# Quectel-2560-v2_1.net
KiCad netlist of a schematic drawn in EAGLE
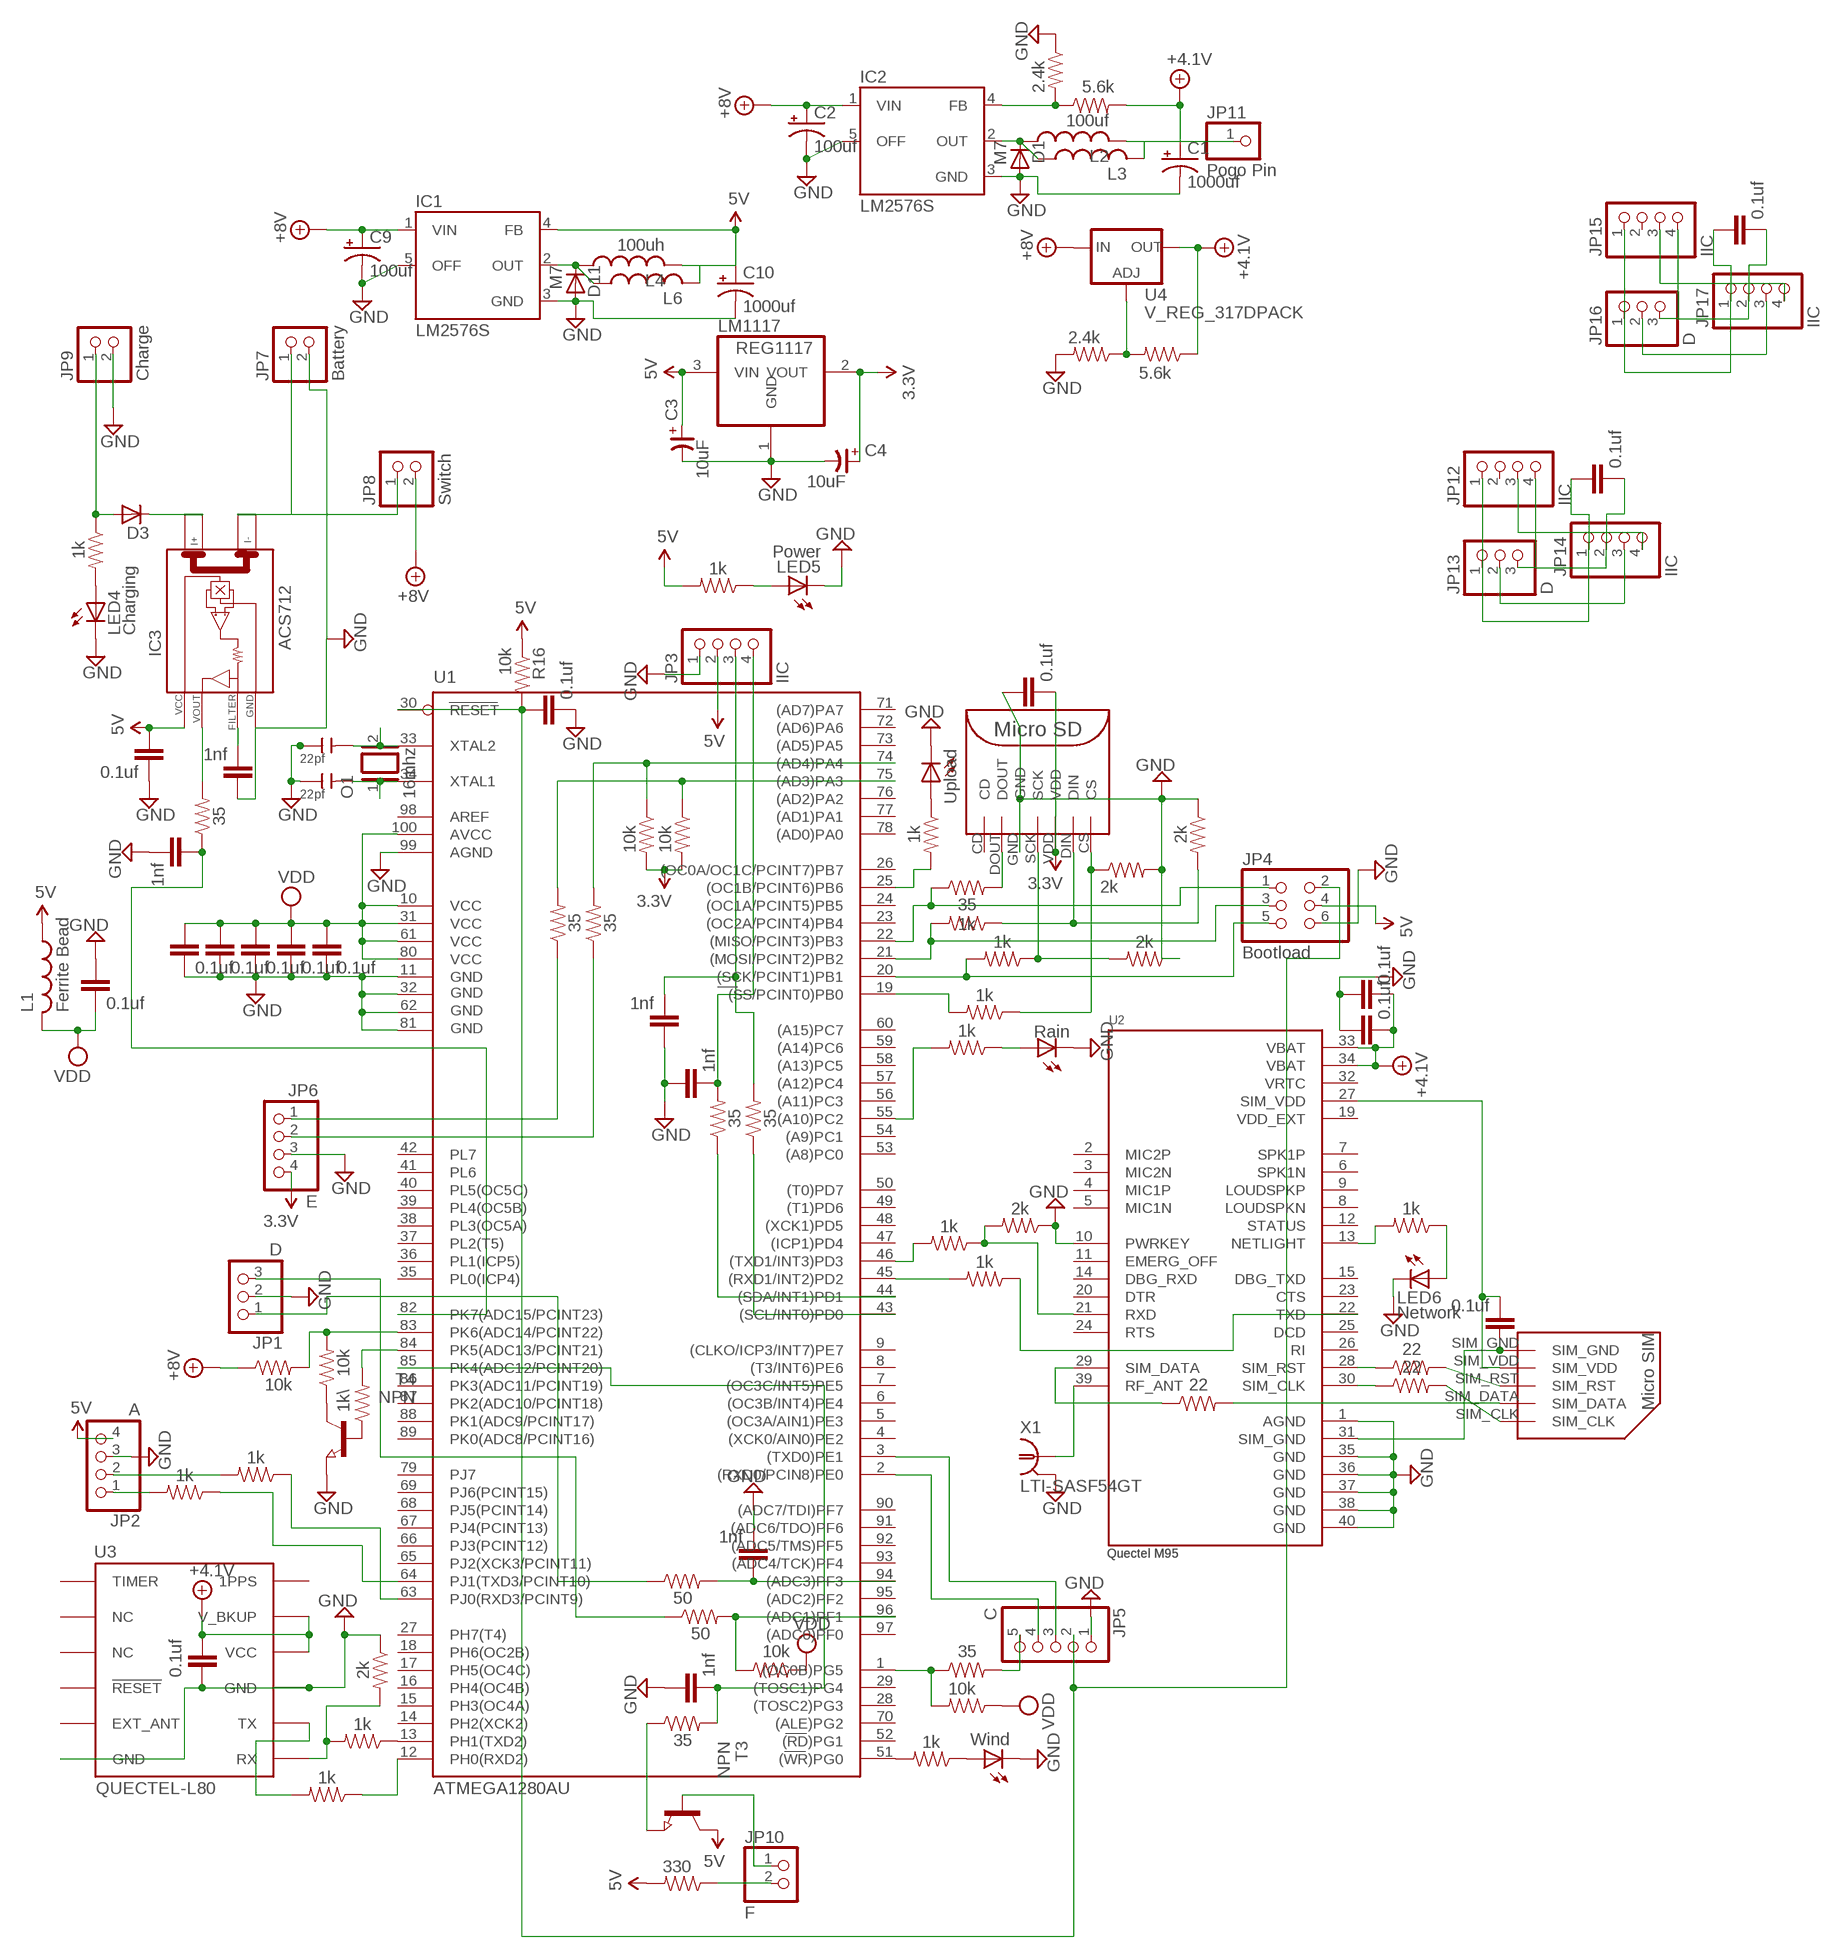
[diagram p0: schematic, sheet 1]

(export (version "E")
  (design (tool "Eeschema 10.0.6"))
  (components
    (comp (ref "C1")
      (value "1000uf")
      (footprint "eagle-import:153CLV-1012")
      (libsource (lib "eagle-import") (part "CPOL-US153CLV-1012"))
    )
    (comp (ref "C2")
      (value "100uf")
      (footprint "eagle-import:CT7343")
      (libsource (lib "eagle-import") (part "CPOL-USCT7343"))
    )
    (comp (ref "C3")
      (value "10uF")
      (footprint "eagle-import:3528_T")
      (libsource (lib "eagle-import") (part "CP-3528"))
    )
    (comp (ref "C4")
      (value "10uF")
      (footprint "eagle-import:3528_T")
      (libsource (lib "eagle-import") (part "CP-3528"))
    )
    (comp (ref "C7")
      (value "22pf")
      (footprint "eagle-import:C0805")
      (fields (field (name "MPN") "CC0805JRNPO9BN220"))
      (libsource (lib "eagle-import") (part "CERAMIC-22PF-50V-5%-NPO(0805)"))
    )
    (comp (ref "C8")
      (value "22pf")
      (footprint "eagle-import:C0805")
      (fields (field (name "MPN") "CC0805JRNPO9BN220"))
      (libsource (lib "eagle-import") (part "CERAMIC-22PF-50V-5%-NPO(0805)"))
    )
    (comp (ref "C9")
      (value "100uf")
      (footprint "eagle-import:CT7343")
      (libsource (lib "eagle-import") (part "CPOL-USCT7343"))
    )
    (comp (ref "C10")
      (value "1000uf")
      (footprint "eagle-import:153CLV-1012")
      (libsource (lib "eagle-import") (part "CPOL-US153CLV-1012"))
    )
    (comp (ref "D1")
      (value "M7")
      (footprint "eagle-import:SOD106A")
      (fields (field (name "MPN") "BYS10/45"))
      (libsource (lib "eagle-import") (part "BYS10"))
    )
    (comp (ref "D3")
      (value "BYS10")
      (footprint "eagle-import:SOD106A")
      (fields (field (name "MPN") "BYS10/45"))
      (libsource (lib "eagle-import") (part "BYS10"))
    )
    (comp (ref "D11")
      (value "M7")
      (footprint "eagle-import:SOD106A")
      (fields (field (name "MPN") "BYS10/45"))
      (libsource (lib "eagle-import") (part "BYS10"))
    )
    (comp (ref "DC1")
      (value "0.1uf")
      (footprint "eagle-import:C0805")
      (libsource (lib "eagle-import") (part "C-EUC0805"))
    )
    (comp (ref "DC2")
      (value "0.1uf")
      (footprint "eagle-import:C0805")
      (libsource (lib "eagle-import") (part "C-EUC0805"))
    )
    (comp (ref "DC3")
      (value "0.1uf")
      (footprint "eagle-import:C0805")
      (libsource (lib "eagle-import") (part "C-EUC0805"))
    )
    (comp (ref "DC4")
      (value "0.1uf")
      (footprint "eagle-import:C0805")
      (libsource (lib "eagle-import") (part "C-EUC0805"))
    )
    (comp (ref "DC5")
      (value "0.1uf")
      (footprint "eagle-import:C0805")
      (libsource (lib "eagle-import") (part "C-EUC0805"))
    )
    (comp (ref "DC6")
      (value "0.1uf")
      (footprint "eagle-import:C0805")
      (libsource (lib "eagle-import") (part "C-EUC0805"))
    )
    (comp (ref "DC7")
      (value "0.1uf")
      (footprint "eagle-import:C0805")
      (libsource (lib "eagle-import") (part "C-EUC0805"))
    )
    (comp (ref "DC8")
      (value "0.1uf")
      (footprint "eagle-import:C0805")
      (libsource (lib "eagle-import") (part "C-EUC0805"))
    )
    (comp (ref "DC9")
      (value "0.1uf")
      (footprint "eagle-import:C0805")
      (libsource (lib "eagle-import") (part "C-EUC0805"))
    )
    (comp (ref "DC10")
      (value "0.1uf")
      (footprint "eagle-import:C0805")
      (libsource (lib "eagle-import") (part "C-EUC0805"))
    )
    (comp (ref "DC11")
      (value "0.1uf")
      (footprint "eagle-import:C0805")
      (libsource (lib "eagle-import") (part "C-EUC0805"))
    )
    (comp (ref "DC12")
      (value "1nf")
      (footprint "eagle-import:C0805")
      (libsource (lib "eagle-import") (part "C-EUC0805"))
    )
    (comp (ref "DC13")
      (value "1nf")
      (footprint "eagle-import:C0805")
      (libsource (lib "eagle-import") (part "C-EUC0805"))
    )
    (comp (ref "DC14")
      (value "1nf")
      (footprint "eagle-import:C0805")
      (libsource (lib "eagle-import") (part "C-EUC0805"))
    )
    (comp (ref "DC15")
      (value "0.1uf")
      (footprint "eagle-import:C0805")
      (libsource (lib "eagle-import") (part "C-EUC0805"))
    )
    (comp (ref "DC16")
      (value "0.1uf")
      (footprint "eagle-import:C0805")
      (libsource (lib "eagle-import") (part "C-EUC0805"))
    )
    (comp (ref "DC17")
      (value "1nf")
      (footprint "eagle-import:C0805")
      (libsource (lib "eagle-import") (part "C-EUC0805"))
    )
    (comp (ref "DC18")
      (value "0.1uf")
      (footprint "eagle-import:C0805")
      (libsource (lib "eagle-import") (part "C-EUC0805"))
    )
    (comp (ref "DC19")
      (value "0.1uf")
      (footprint "eagle-import:C0805")
      (libsource (lib "eagle-import") (part "C-EUC0805"))
    )
    (comp (ref "DC20")
      (value "1nf")
      (footprint "eagle-import:C0805")
      (libsource (lib "eagle-import") (part "C-EUC0805"))
    )
    (comp (ref "DC21")
      (value "1nf")
      (footprint "eagle-import:C0805")
      (libsource (lib "eagle-import") (part "C-EUC0805"))
    )
    (comp (ref "IC1")
      (value "LM2576S")
      (footprint "eagle-import:TO263-5")
      (libsource (lib "eagle-import") (part "LM2576S"))
    )
    (comp (ref "IC2")
      (value "LM2576S")
      (footprint "eagle-import:TO263-5")
      (libsource (lib "eagle-import") (part "LM2576S"))
    )
    (comp (ref "IC3")
      (value "ACS712")
      (footprint "eagle-import:SO08")
      (libsource (lib "eagle-import") (part "ACS712"))
    )
    (comp (ref "JP1")
      (value "D")
      (footprint "eagle-import:1X03")
      (libsource (lib "eagle-import") (part "PINHD-1X3"))
    )
    (comp (ref "JP2")
      (value "A")
      (footprint "eagle-import:1X04")
      (libsource (lib "eagle-import") (part "PINHD-1X4"))
    )
    (comp (ref "JP3")
      (value "IIC")
      (footprint "eagle-import:1X04")
      (libsource (lib "eagle-import") (part "PINHD-1X4"))
    )
    (comp (ref "JP4")
      (value "Bootload")
      (footprint "eagle-import:2X03")
      (libsource (lib "eagle-import") (part "PINHD-2X3"))
    )
    (comp (ref "JP5")
      (value "C")
      (footprint "eagle-import:1X05")
      (libsource (lib "eagle-import") (part "PINHD-1X5"))
    )
    (comp (ref "JP6")
      (value "E")
      (footprint "eagle-import:1X04")
      (libsource (lib "eagle-import") (part "PINHD-1X4"))
    )
    (comp (ref "JP7")
      (value "Battery")
      (footprint "eagle-import:1X02")
      (libsource (lib "eagle-import") (part "PINHD-1X2"))
    )
    (comp (ref "JP8")
      (value "Switch")
      (footprint "eagle-import:1X02")
      (libsource (lib "eagle-import") (part "PINHD-1X2"))
    )
    (comp (ref "JP9")
      (value "Charge")
      (footprint "eagle-import:1X02")
      (libsource (lib "eagle-import") (part "PINHD-1X2"))
    )
    (comp (ref "JP10")
      (value "F")
      (footprint "eagle-import:1X02")
      (libsource (lib "eagle-import") (part "PINHD-1X2"))
    )
    (comp (ref "JP11")
      (value "Pogo Pin")
      (footprint "eagle-import:1X01")
      (libsource (lib "eagle-import") (part "PINHD-1X1"))
    )
    (comp (ref "JP12")
      (value "IIC")
      (footprint "eagle-import:1X04")
      (libsource (lib "eagle-import") (part "PINHD-1X4"))
    )
    (comp (ref "JP13")
      (value "D")
      (footprint "eagle-import:1X03")
      (libsource (lib "eagle-import") (part "PINHD-1X3"))
    )
    (comp (ref "JP14")
      (value "IIC")
      (footprint "eagle-import:1X04")
      (libsource (lib "eagle-import") (part "PINHD-1X4"))
    )
    (comp (ref "JP15")
      (value "IIC")
      (footprint "eagle-import:1X04")
      (libsource (lib "eagle-import") (part "PINHD-1X4"))
    )
    (comp (ref "JP16")
      (value "D")
      (footprint "eagle-import:1X03")
      (libsource (lib "eagle-import") (part "PINHD-1X3"))
    )
    (comp (ref "JP17")
      (value "IIC")
      (footprint "eagle-import:1X04")
      (libsource (lib "eagle-import") (part "PINHD-1X4"))
    )
    (comp (ref "L1")
      (value "Ferrite Bead")
      (footprint "eagle-import:L2012C")
      (libsource (lib "eagle-import") (part "L-USL2012C"))
    )
    (comp (ref "L2")
      (value "100uf")
      (footprint "eagle-import:PIS2816")
      (libsource (lib "eagle-import") (part "L-USPIS2816"))
    )
    (comp (ref "L3")
      (value "L-US6000-XXX-RC")
      (footprint "eagle-import:6000-XXXX-RC")
      (libsource (lib "eagle-import") (part "L-US6000-XXX-RC"))
    )
    (comp (ref "L4")
      (value "100uh")
      (footprint "eagle-import:PIS2816")
      (libsource (lib "eagle-import") (part "L-USPIS2816"))
    )
    (comp (ref "L6")
      (value "L-US6000-XXX-RC")
      (footprint "eagle-import:6000-XXXX-RC")
      (libsource (lib "eagle-import") (part "L-US6000-XXX-RC"))
    )
    (comp (ref "LED1")
      (value "Rain")
      (footprint "eagle-import:CHIP-LED0805")
      (libsource (lib "eagle-import") (part "LEDCHIP-LED0805"))
    )
    (comp (ref "LED2")
      (value "Upload")
      (footprint "eagle-import:CHIP-LED0805")
      (libsource (lib "eagle-import") (part "LEDCHIP-LED0805"))
    )
    (comp (ref "LED3")
      (value "Wind")
      (footprint "eagle-import:CHIP-LED0805")
      (libsource (lib "eagle-import") (part "LEDCHIP-LED0805"))
    )
    (comp (ref "LED4")
      (value "Charging")
      (footprint "eagle-import:CHIP-LED0805")
      (libsource (lib "eagle-import") (part "LEDCHIP-LED0805"))
    )
    (comp (ref "LED5")
      (value "Power")
      (footprint "eagle-import:CHIP-LED0805")
      (libsource (lib "eagle-import") (part "LEDCHIP-LED0805"))
    )
    (comp (ref "LED6")
      (value "Network")
      (footprint "eagle-import:CHIP-LED0805")
      (libsource (lib "eagle-import") (part "LEDCHIP-LED0805"))
    )
    (comp (ref "LM1117")
      (value "REG1117")
      (footprint "eagle-import:SOT223")
      (libsource (lib "eagle-import") (part "REG1117"))
    )
    (comp (ref "O1")
      (value "16mhz")
      (footprint "eagle-import:QS")
      (libsource (lib "eagle-import") (part "XTAL/S"))
    )
    (comp (ref "R1")
      (value "35")
      (footprint "eagle-import:0805")
      (libsource (lib "eagle-import") (part "RESISTOR0805-RES"))
    )
    (comp (ref "R4")
      (value "2k")
      (footprint "eagle-import:0805")
      (libsource (lib "eagle-import") (part "RESISTOR0805-RES"))
    )
    (comp (ref "R5")
      (value "35")
      (footprint "eagle-import:0805")
      (libsource (lib "eagle-import") (part "RESISTOR0805-RES"))
    )
    (comp (ref "R6")
      (value "1k")
      (footprint "eagle-import:0805")
      (libsource (lib "eagle-import") (part "RESISTOR0805-RES"))
    )
    (comp (ref "R7")
      (value "1k")
      (footprint "eagle-import:0805")
      (libsource (lib "eagle-import") (part "RESISTOR0805-RES"))
    )
    (comp (ref "R8")
      (value "1k")
      (footprint "eagle-import:0805")
      (libsource (lib "eagle-import") (part "RESISTOR0805-RES"))
    )
    (comp (ref "R9")
      (value "2k")
      (footprint "eagle-import:0805")
      (libsource (lib "eagle-import") (part "RESISTOR0805-RES"))
    )
    (comp (ref "R10")
      (value "22")
      (footprint "eagle-import:0805")
      (libsource (lib "eagle-import") (part "RESISTOR0805-RES"))
    )
    (comp (ref "R11")
      (value "22")
      (footprint "eagle-import:0805")
      (libsource (lib "eagle-import") (part "RESISTOR0805-RES"))
    )
    (comp (ref "R12")
      (value "1k")
      (footprint "eagle-import:0805")
      (libsource (lib "eagle-import") (part "RESISTOR0805-RES"))
    )
    (comp (ref "R13")
      (value "1k")
      (footprint "eagle-import:0805")
      (libsource (lib "eagle-import") (part "RESISTOR0805-RES"))
    )
    (comp (ref "R14")
      (value "1k")
      (footprint "eagle-import:0805")
      (libsource (lib "eagle-import") (part "RESISTOR0805-RES"))
    )
    (comp (ref "R15")
      (value "1k")
      (footprint "eagle-import:0805")
      (libsource (lib "eagle-import") (part "RESISTOR0805-RES"))
    )
    (comp (ref "R16")
      (value "10k")
      (footprint "eagle-import:0805")
      (libsource (lib "eagle-import") (part "RESISTOR0805-RES"))
    )
    (comp (ref "R17")
      (value "1k")
      (footprint "eagle-import:0805")
      (libsource (lib "eagle-import") (part "RESISTOR0805-RES"))
    )
    (comp (ref "R18")
      (value "1k")
      (footprint "eagle-import:0805")
      (libsource (lib "eagle-import") (part "RESISTOR0805-RES"))
    )
    (comp (ref "R19")
      (value "35")
      (footprint "eagle-import:0805")
      (libsource (lib "eagle-import") (part "RESISTOR0805-RES"))
    )
    (comp (ref "R20")
      (value "10k")
      (footprint "eagle-import:0805")
      (libsource (lib "eagle-import") (part "RESISTOR0805-RES"))
    )
    (comp (ref "R21")
      (value "50")
      (footprint "eagle-import:0805")
      (libsource (lib "eagle-import") (part "RESISTOR0805-RES"))
    )
    (comp (ref "R22")
      (value "35")
      (footprint "eagle-import:0805")
      (libsource (lib "eagle-import") (part "RESISTOR0805-RES"))
    )
    (comp (ref "R23")
      (value "2k")
      (footprint "eagle-import:0805")
      (libsource (lib "eagle-import") (part "RESISTOR0805-RES"))
    )
    (comp (ref "R24")
      (value "2k")
      (footprint "eagle-import:0805")
      (libsource (lib "eagle-import") (part "RESISTOR0805-RES"))
    )
    (comp (ref "R25")
      (value "1k")
      (footprint "eagle-import:0805")
      (libsource (lib "eagle-import") (part "RESISTOR0805-RES"))
    )
    (comp (ref "R26")
      (value "1k")
      (footprint "eagle-import:0805")
      (libsource (lib "eagle-import") (part "RESISTOR0805-RES"))
    )
    (comp (ref "R27")
      (value "1k")
      (footprint "eagle-import:0805")
      (libsource (lib "eagle-import") (part "RESISTOR0805-RES"))
    )
    (comp (ref "R28")
      (value "1k")
      (footprint "eagle-import:0805")
      (libsource (lib "eagle-import") (part "RESISTOR0805-RES"))
    )
    (comp (ref "R29")
      (value "2k")
      (footprint "eagle-import:0805")
      (libsource (lib "eagle-import") (part "RESISTOR0805-RES"))
    )
    (comp (ref "R30")
      (value "35")
      (footprint "eagle-import:0805")
      (libsource (lib "eagle-import") (part "RESISTOR0805-RES"))
    )
    (comp (ref "R31")
      (value "50")
      (footprint "eagle-import:0805")
      (libsource (lib "eagle-import") (part "RESISTOR0805-RES"))
    )
    (comp (ref "R32")
      (value "1k")
      (footprint "eagle-import:0805")
      (libsource (lib "eagle-import") (part "RESISTOR0805-RES"))
    )
    (comp (ref "R33")
      (value "1k")
      (footprint "eagle-import:0805")
      (libsource (lib "eagle-import") (part "RESISTOR0805-RES"))
    )
    (comp (ref "R34")
      (value "10k")
      (footprint "eagle-import:0805")
      (libsource (lib "eagle-import") (part "RESISTOR0805-RES"))
    )
    (comp (ref "R35")
      (value "35")
      (footprint "eagle-import:0805")
      (libsource (lib "eagle-import") (part "RESISTOR0805-RES"))
    )
    (comp (ref "R36")
      (value "10k")
      (footprint "eagle-import:0805")
      (libsource (lib "eagle-import") (part "RESISTOR0805-RES"))
    )
    (comp (ref "R39")
      (value "35")
      (footprint "eagle-import:0805")
      (libsource (lib "eagle-import") (part "RESISTOR0805-RES"))
    )
    (comp (ref "R40")
      (value "10k")
      (footprint "eagle-import:0805")
      (libsource (lib "eagle-import") (part "RESISTOR0805-RES"))
    )
    (comp (ref "R41")
      (value "330")
      (footprint "eagle-import:0805")
      (libsource (lib "eagle-import") (part "RESISTOR0805-RES"))
    )
    (comp (ref "R42")
      (value "35")
      (footprint "eagle-import:0805")
      (libsource (lib "eagle-import") (part "RESISTOR0805-RES"))
    )
    (comp (ref "R43")
      (value "10k")
      (footprint "eagle-import:0805")
      (libsource (lib "eagle-import") (part "RESISTOR0805-RES"))
    )
    (comp (ref "R44")
      (value "10k")
      (footprint "eagle-import:0805")
      (libsource (lib "eagle-import") (part "RESISTOR0805-RES"))
    )
    (comp (ref "R45")
      (value "2.4k")
      (footprint "eagle-import:0805")
      (libsource (lib "eagle-import") (part "RESISTOR0805-RES"))
    )
    (comp (ref "R46")
      (value "5.6k")
      (footprint "eagle-import:0805")
      (libsource (lib "eagle-import") (part "RESISTOR0805-RES"))
    )
    (comp (ref "R47")
      (value "22")
      (footprint "eagle-import:0805")
      (libsource (lib "eagle-import") (part "RESISTOR0805-RES"))
    )
    (comp (ref "R48")
      (value "1k\\")
      (footprint "eagle-import:0805")
      (libsource (lib "eagle-import") (part "RESISTOR0805-RES"))
    )
    (comp (ref "R49")
      (value "2.4k")
      (footprint "eagle-import:0805")
      (libsource (lib "eagle-import") (part "RESISTOR0805-RES"))
    )
    (comp (ref "R50")
      (value "5.6k")
      (footprint "eagle-import:0805")
      (libsource (lib "eagle-import") (part "RESISTOR0805-RES"))
    )
    (comp (ref "T3")
      (value "NPN")
      (footprint "eagle-import:SOT23")
      (libsource (lib "eagle-import") (part "NPN-TRANSISTOR_SOT23"))
    )
    (comp (ref "T4")
      (value "NPN")
      (footprint "eagle-import:SOT23")
      (libsource (lib "eagle-import") (part "NPN-TRANSISTOR_SOT23"))
    )
    (comp (ref "U$1")
      (value "MICROSD")
      (footprint "eagle-import:MICROSD")
      (libsource (lib "eagle-import") (part "MICROSD"))
    )
    (comp (ref "U$2")
      (value "MICROSIM")
      (footprint "eagle-import:MICROSIM")
      (libsource (lib "eagle-import") (part "MICROSIM"))
    )
    (comp (ref "U1")
      (value "ATMEGA1280AU")
      (footprint "eagle-import:TQFP100")
      (libsource (lib "eagle-import") (part "ATMEGA2560AU"))
    )
    (comp (ref "U2")
      (value "Quectel M95")
      (footprint "eagle-import:XCVR_M95")
      (libsource (lib "eagle-import") (part "M95"))
    )
    (comp (ref "U3")
      (value "QUECTEL-L80")
      (footprint "eagle-import:QUECTEL-L80")
      (libsource (lib "eagle-import") (part "QUECTEL-L80"))
    )
    (comp (ref "U4")
      (value "V_REG_317DPACK")
      (footprint "eagle-import:V-REG_DPACK")
      (libsource (lib "eagle-import") (part "V_REG_317DPACK"))
    )
    (comp (ref "X1")
      (value "LTI-SASF54GT")
      (footprint "eagle-import:LTI-SASF54GT")
      (libsource (lib "eagle-import") (part "LTI-SASF54GT"))
    )
  )
  (nets
    (net (code "1") (name "+4.1V") (class "Default")
      (node (ref "C1") (pin "+") (pinfunction "+_+") (pintype "passive"))
      (node (ref "DC16") (pin "1") (pinfunction "1_1") (pintype "passive"))
      (node (ref "DC6") (pin "2") (pinfunction "2_2") (pintype "passive"))
      (node (ref "DC7") (pin "2") (pinfunction "2_2") (pintype "passive"))
      (node (ref "JP11") (pin "1") (pinfunction "1_1") (pintype "passive"))
      (node (ref "L2") (pin "2") (pinfunction "2_2") (pintype "passive"))
      (node (ref "L3") (pin "2") (pinfunction "2_2") (pintype "passive"))
      (node (ref "R46") (pin "2") (pinfunction "2_2") (pintype "passive"))
      (node (ref "R50") (pin "1") (pinfunction "1_1") (pintype "passive"))
      (node (ref "U2") (pin "33") (pinfunction "VBAT_33") (pintype "power_in"))
      (node (ref "U2") (pin "34") (pinfunction "VBAT_34") (pintype "power_in"))
      (node (ref "U3") (pin "4") (pinfunction "VCC_4") (pintype "power_in"))
      (node (ref "U3") (pin "5") (pinfunction "V_BKUP_5") (pintype "power_in"))
      (node (ref "U4") (pin "4") (pinfunction "OUT_4") (pintype "output"))
    )
    (net (code "2") (name "+8V") (class "Default")
      (node (ref "C2") (pin "+") (pinfunction "+_+") (pintype "passive"))
      (node (ref "C9") (pin "+") (pinfunction "+_+") (pintype "passive"))
      (node (ref "IC1") (pin "1") (pinfunction "VIN_1") (pintype "power_in"))
      (node (ref "IC2") (pin "1") (pinfunction "VIN_1") (pintype "power_in"))
      (node (ref "JP8") (pin "2") (pinfunction "2_2") (pintype "passive"))
      (node (ref "R43") (pin "1") (pinfunction "1_1") (pintype "passive"))
      (node (ref "U4") (pin "3") (pinfunction "IN_3") (pintype "input"))
    )
    (net (code "3") (name "/VDD_EXT") (class "Default")
      (node (ref "U2") (pin "19") (pinfunction "VDD_EXT_19") (pintype "power_in"))
    )
    (net (code "4") (name "/VRTC") (class "Default")
      (node (ref "U2") (pin "32") (pinfunction "VRTC_32") (pintype "power_in"))
    )
    (net (code "5") (name "3.3V") (class "Default")
      (node (ref "C4") (pin "+") (pinfunction "+_+") (pintype "passive"))
      (node (ref "DC10") (pin "2") (pinfunction "2_2") (pintype "passive"))
      (node (ref "JP6") (pin "4") (pinfunction "4_4") (pintype "passive"))
      (node (ref "LM1117") (pin "2") (pinfunction "VOUT_2") (pintype "output"))
      (node (ref "R34") (pin "2") (pinfunction "2_2") (pintype "passive"))
      (node (ref "R36") (pin "2") (pinfunction "2_2") (pintype "passive"))
      (node (ref "U$1") (pin "VDD") (pinfunction "VDD_VDD") (pintype "power_in"))
    )
    (net (code "6") (name "5V") (class "Default")
      (node (ref "C10") (pin "+") (pinfunction "+_+") (pintype "passive"))
      (node (ref "C3") (pin "+") (pinfunction "+_+") (pintype "passive"))
      (node (ref "DC19") (pin "2") (pinfunction "2_2") (pintype "passive"))
      (node (ref "IC1") (pin "4") (pinfunction "FB_4") (pintype "input"))
      (node (ref "IC3") (pin "8") (pinfunction "VCC_8") (pintype "power_in"))
      (node (ref "JP2") (pin "4") (pinfunction "4_4") (pintype "passive"))
      (node (ref "JP3") (pin "2") (pinfunction "2_2") (pintype "passive"))
      (node (ref "JP4") (pin "4") (pinfunction "4_4") (pintype "passive"))
      (node (ref "L1") (pin "1") (pinfunction "1_1") (pintype "passive"))
      (node (ref "L4") (pin "2") (pinfunction "2_2") (pintype "passive"))
      (node (ref "L6") (pin "2") (pinfunction "2_2") (pintype "passive"))
      (node (ref "LM1117") (pin "3") (pinfunction "VIN_3") (pintype "input"))
      (node (ref "R16") (pin "1") (pinfunction "1_1") (pintype "passive"))
      (node (ref "R18") (pin "2") (pinfunction "2_2") (pintype "passive"))
      (node (ref "R41") (pin "2") (pinfunction "2_2") (pintype "passive"))
      (node (ref "T3") (pin "3") (pinfunction "C_3") (pintype "passive"))
    )
    (net (code "7") (name "GND") (class "Default")
      (node (ref "C1") (pin "-") (pinfunction "-_-") (pintype "passive"))
      (node (ref "C10") (pin "-") (pinfunction "-_-") (pintype "passive"))
      (node (ref "C2") (pin "-") (pinfunction "-_-") (pintype "passive"))
      (node (ref "C3") (pin "-") (pinfunction "-_-") (pintype "passive"))
      (node (ref "C4") (pin "-") (pinfunction "-_-") (pintype "passive"))
      (node (ref "C7") (pin "1") (pinfunction "1_1") (pintype "passive"))
      (node (ref "C8") (pin "1") (pinfunction "1_1") (pintype "passive"))
      (node (ref "C9") (pin "-") (pinfunction "-_-") (pintype "passive"))
      (node (ref "D1") (pin "A") (pinfunction "A_A") (pintype "passive"))
      (node (ref "D11") (pin "A") (pinfunction "A_A") (pintype "passive"))
      (node (ref "DC1") (pin "2") (pinfunction "2_2") (pintype "passive"))
      (node (ref "DC10") (pin "1") (pinfunction "1_1") (pintype "passive"))
      (node (ref "DC11") (pin "2") (pinfunction "2_2") (pintype "passive"))
      (node (ref "DC12") (pin "1") (pinfunction "1_1") (pintype "passive"))
      (node (ref "DC13") (pin "1") (pinfunction "1_1") (pintype "passive"))
      (node (ref "DC14") (pin "1") (pinfunction "1_1") (pintype "passive"))
      (node (ref "DC16") (pin "2") (pinfunction "2_2") (pintype "passive"))
      (node (ref "DC17") (pin "2") (pinfunction "2_2") (pintype "passive"))
      (node (ref "DC18") (pin "1") (pinfunction "1_1") (pintype "passive"))
      (node (ref "DC19") (pin "1") (pinfunction "1_1") (pintype "passive"))
      (node (ref "DC2") (pin "2") (pinfunction "2_2") (pintype "passive"))
      (node (ref "DC20") (pin "1") (pinfunction "1_1") (pintype "passive"))
      (node (ref "DC21") (pin "2") (pinfunction "2_2") (pintype "passive"))
      (node (ref "DC3") (pin "2") (pinfunction "2_2") (pintype "passive"))
      (node (ref "DC4") (pin "2") (pinfunction "2_2") (pintype "passive"))
      (node (ref "DC5") (pin "2") (pinfunction "2_2") (pintype "passive"))
      (node (ref "DC6") (pin "1") (pinfunction "1_1") (pintype "passive"))
      (node (ref "DC7") (pin "1") (pinfunction "1_1") (pintype "passive"))
      (node (ref "IC1") (pin "3") (pinfunction "GND_3") (pintype "power_in"))
      (node (ref "IC1") (pin "5") (pinfunction "OFF_5") (pintype "input"))
      (node (ref "IC2") (pin "3") (pinfunction "GND_3") (pintype "power_in"))
      (node (ref "IC2") (pin "5") (pinfunction "OFF_5") (pintype "input"))
      (node (ref "IC3") (pin "5") (pinfunction "GND_5") (pintype "power_in"))
      (node (ref "JP1") (pin "2") (pinfunction "2_2") (pintype "passive"))
      (node (ref "JP2") (pin "3") (pinfunction "3_3") (pintype "passive"))
      (node (ref "JP3") (pin "1") (pinfunction "1_1") (pintype "passive"))
      (node (ref "JP4") (pin "6") (pinfunction "6_6") (pintype "passive"))
      (node (ref "JP5") (pin "1") (pinfunction "1_1") (pintype "passive"))
      (node (ref "JP6") (pin "3") (pinfunction "3_3") (pintype "passive"))
      (node (ref "JP7") (pin "2") (pinfunction "2_2") (pintype "passive"))
      (node (ref "JP9") (pin "2") (pinfunction "2_2") (pintype "passive"))
      (node (ref "LED1") (pin "C") (pinfunction "C_C") (pintype "passive"))
      (node (ref "LED2") (pin "C") (pinfunction "C_C") (pintype "passive"))
      (node (ref "LED3") (pin "C") (pinfunction "C_C") (pintype "passive"))
      (node (ref "LED4") (pin "C") (pinfunction "C_C") (pintype "passive"))
      (node (ref "LED5") (pin "C") (pinfunction "C_C") (pintype "passive"))
      (node (ref "LED6") (pin "C") (pinfunction "C_C") (pintype "passive"))
      (node (ref "LM1117") (pin "1") (pinfunction "GND_1") (pintype "power_in"))
      (node (ref "R23") (pin "2") (pinfunction "2_2") (pintype "passive"))
      (node (ref "R24") (pin "1") (pinfunction "1_1") (pintype "passive"))
      (node (ref "R29") (pin "1") (pinfunction "1_1") (pintype "passive"))
      (node (ref "R4") (pin "1") (pinfunction "1_1") (pintype "passive"))
      (node (ref "R45") (pin "1") (pinfunction "1_1") (pintype "passive"))
      (node (ref "R49") (pin "2") (pinfunction "2_2") (pintype "passive"))
      (node (ref "R9") (pin "1") (pinfunction "1_1") (pintype "passive"))
      (node (ref "T4") (pin "2") (pinfunction "E_2") (pintype "passive"))
      (node (ref "U$1") (pin "GND") (pinfunction "GND_GND") (pintype "power_in"))
      (node (ref "U1") (pin "11") (pinfunction "GND_11") (pintype "power_in"))
      (node (ref "U1") (pin "32") (pinfunction "GND1_32") (pintype "power_in"))
      (node (ref "U1") (pin "62") (pinfunction "GND2_62") (pintype "power_in"))
      (node (ref "U1") (pin "81") (pinfunction "GND3_81") (pintype "power_in"))
      (node (ref "U1") (pin "99") (pinfunction "AGND_99") (pintype "power_in"))
      (node (ref "U2") (pin "1") (pinfunction "AGND_1") (pintype "power_in"))
      (node (ref "U2") (pin "10") (pinfunction "PWRKEY_10") (pintype "input"))
      (node (ref "U2") (pin "35") (pinfunction "GND_35") (pintype "power_in"))
      (node (ref "U2") (pin "36") (pinfunction "GND_36") (pintype "power_in"))
      (node (ref "U2") (pin "37") (pinfunction "GND_37") (pintype "power_in"))
      (node (ref "U2") (pin "38") (pinfunction "GND_38") (pintype "input"))
      (node (ref "U2") (pin "40") (pinfunction "GND_40") (pintype "power_in"))
      (node (ref "U3") (pin "12") (pinfunction "GND_12") (pintype "power_in"))
      (node (ref "U3") (pin "3") (pinfunction "GND_3") (pintype "power_in"))
      (node (ref "X1") (pin "2") (pinfunction "2_2") (pintype "passive"))
      (node (ref "X1") (pin "3") (pinfunction "2_3") (pintype "passive"))
      (node (ref "X1") (pin "4") (pinfunction "2_4") (pintype "passive"))
      (node (ref "X1") (pin "5") (pinfunction "2_5") (pintype "passive"))
    )
    (net (code "8") (name "Net-(D3-PadA)") (class "Default")
      (node (ref "D3") (pin "A") (pinfunction "A_A") (pintype "passive"))
      (node (ref "JP9") (pin "1") (pinfunction "1_1") (pintype "passive"))
      (node (ref "R26") (pin "1") (pinfunction "1_1") (pintype "passive"))
    )
    (net (code "9") (name "Net-(DC8-Pad1)") (class "Default")
      (node (ref "DC8") (pin "1") (pinfunction "1_1") (pintype "passive"))
      (node (ref "JP12") (pin "1") (pinfunction "1_1") (pintype "passive"))
      (node (ref "JP13") (pin "1") (pinfunction "1_1") (pintype "passive"))
      (node (ref "JP14") (pin "1") (pinfunction "1_1") (pintype "passive"))
    )
    (net (code "10") (name "Net-(DC8-Pad2)") (class "Default")
      (node (ref "DC8") (pin "2") (pinfunction "2_2") (pintype "passive"))
      (node (ref "JP12") (pin "4") (pinfunction "4_4") (pintype "passive"))
      (node (ref "JP13") (pin "3") (pinfunction "3_3") (pintype "passive"))
      (node (ref "JP14") (pin "2") (pinfunction "2_2") (pintype "passive"))
    )
    (net (code "11") (name "Net-(DC9-Pad1)") (class "Default")
      (node (ref "DC9") (pin "1") (pinfunction "1_1") (pintype "passive"))
      (node (ref "JP15") (pin "1") (pinfunction "1_1") (pintype "passive"))
      (node (ref "JP16") (pin "1") (pinfunction "1_1") (pintype "passive"))
      (node (ref "JP17") (pin "1") (pinfunction "1_1") (pintype "passive"))
    )
    (net (code "12") (name "Net-(DC9-Pad2)") (class "Default")
      (node (ref "DC9") (pin "2") (pinfunction "2_2") (pintype "passive"))
      (node (ref "JP15") (pin "4") (pinfunction "4_4") (pintype "passive"))
      (node (ref "JP16") (pin "3") (pinfunction "3_3") (pintype "passive"))
      (node (ref "JP17") (pin "2") (pinfunction "2_2") (pintype "passive"))
    )
    (net (code "13") (name "Net-(DC12-Pad2)") (class "Default")
      (node (ref "DC12") (pin "2") (pinfunction "2_2") (pintype "passive"))
      (node (ref "JP3") (pin "4") (pinfunction "4_4") (pintype "passive"))
      (node (ref "R5") (pin "2") (pinfunction "2_2") (pintype "passive"))
    )
    (net (code "14") (name "Net-(DC13-Pad2)") (class "Default")
      (node (ref "DC13") (pin "2") (pinfunction "2_2") (pintype "passive"))
      (node (ref "JP3") (pin "3") (pinfunction "3_3") (pintype "passive"))
      (node (ref "R30") (pin "2") (pinfunction "2_2") (pintype "passive"))
    )
    (net (code "15") (name "Net-(IC1-OUT)") (class "Default")
      (node (ref "D11") (pin "K") (pinfunction "K_K") (pintype "passive"))
      (node (ref "IC1") (pin "2") (pinfunction "OUT_2") (pintype "output"))
      (node (ref "L4") (pin "1") (pinfunction "1_1") (pintype "passive"))
      (node (ref "L6") (pin "1") (pinfunction "1_1") (pintype "passive"))
    )
    (net (code "16") (name "Net-(IC2-FB)") (class "Default")
      (node (ref "IC2") (pin "4") (pinfunction "FB_4") (pintype "input"))
      (node (ref "R45") (pin "2") (pinfunction "2_2") (pintype "passive"))
      (node (ref "R46") (pin "1") (pinfunction "1_1") (pintype "passive"))
    )
    (net (code "17") (name "Net-(IC2-OUT)") (class "Default")
      (node (ref "D1") (pin "K") (pinfunction "K_K") (pintype "passive"))
      (node (ref "IC2") (pin "2") (pinfunction "OUT_2") (pintype "output"))
      (node (ref "L2") (pin "1") (pinfunction "1_1") (pintype "passive"))
      (node (ref "L3") (pin "1") (pinfunction "1_1") (pintype "passive"))
    )
    (net (code "18") (name "Net-(IC3-FILTER)") (class "Default")
      (node (ref "DC20") (pin "2") (pinfunction "2_2") (pintype "passive"))
      (node (ref "IC3") (pin "6") (pinfunction "FILTER_6") (pintype "bidirectional"))
    )
    (net (code "19") (name "Net-(IC3-I+_0)") (class "Default")
      (node (ref "D3") (pin "K") (pinfunction "K_K") (pintype "passive"))
      (node (ref "IC3") (pin "1") (pinfunction "I+_0_1") (pintype "bidirectional"))
    )
    (net (code "20") (name "Net-(IC3-I-_1)") (class "Default")
      (node (ref "IC3") (pin "4") (pinfunction "I-_1_4") (pintype "bidirectional"))
      (node (ref "JP7") (pin "1") (pinfunction "1_1") (pintype "passive"))
      (node (ref "JP8") (pin "1") (pinfunction "1_1") (pintype "passive"))
    )
    (net (code "21") (name "Net-(IC3-VOUT)") (class "Default")
      (node (ref "IC3") (pin "7") (pinfunction "VOUT_7") (pintype "output"))
      (node (ref "R1") (pin "2") (pinfunction "2_2") (pintype "passive"))
    )
    (net (code "22") (name "Net-(JP1-Pad1)") (class "Default")
      (node (ref "JP1") (pin "1") (pinfunction "1_1") (pintype "passive"))
      (node (ref "R21") (pin "1") (pinfunction "1_1") (pintype "passive"))
    )
    (net (code "23") (name "Net-(JP1-Pad3)") (class "Default")
      (node (ref "JP1") (pin "3") (pinfunction "3_3") (pintype "passive"))
      (node (ref "R31") (pin "1") (pinfunction "1_1") (pintype "passive"))
    )
    (net (code "24") (name "Net-(JP2-Pad1)") (class "Default")
      (node (ref "JP2") (pin "1") (pinfunction "1_1") (pintype "passive"))
      (node (ref "R33") (pin "2") (pinfunction "2_2") (pintype "passive"))
    )
    (net (code "25") (name "Net-(JP2-Pad2)") (class "Default")
      (node (ref "JP2") (pin "2") (pinfunction "2_2") (pintype "passive"))
      (node (ref "R32") (pin "2") (pinfunction "2_2") (pintype "passive"))
    )
    (net (code "26") (name "Net-(JP5-Pad5)") (class "Default")
      (node (ref "JP5") (pin "5") (pinfunction "5_5") (pintype "passive"))
      (node (ref "R39") (pin "2") (pinfunction "2_2") (pintype "passive"))
    )
    (net (code "27") (name "Net-(JP6-Pad1)") (class "Default")
      (node (ref "JP6") (pin "1") (pinfunction "1_1") (pintype "passive"))
      (node (ref "R22") (pin "1") (pinfunction "1_1") (pintype "passive"))
    )
    (net (code "28") (name "Net-(JP6-Pad2)") (class "Default")
      (node (ref "JP6") (pin "2") (pinfunction "2_2") (pintype "passive"))
      (node (ref "R19") (pin "1") (pinfunction "1_1") (pintype "passive"))
    )
    (net (code "29") (name "Net-(JP10-Pad2)") (class "Default")
      (node (ref "JP10") (pin "2") (pinfunction "2_2") (pintype "passive"))
      (node (ref "R41") (pin "1") (pinfunction "1_1") (pintype "passive"))
    )
    (net (code "30") (name "Net-(JP12-Pad3)") (class "Default")
      (node (ref "JP12") (pin "3") (pinfunction "3_3") (pintype "passive"))
      (node (ref "JP14") (pin "4") (pinfunction "4_4") (pintype "passive"))
    )
    (net (code "31") (name "Net-(JP13-Pad2)") (class "Default")
      (node (ref "JP13") (pin "2") (pinfunction "2_2") (pintype "passive"))
      (node (ref "JP14") (pin "3") (pinfunction "3_3") (pintype "passive"))
    )
    (net (code "32") (name "Net-(JP15-Pad3)") (class "Default")
      (node (ref "JP15") (pin "3") (pinfunction "3_3") (pintype "passive"))
      (node (ref "JP17") (pin "4") (pinfunction "4_4") (pintype "passive"))
    )
    (net (code "33") (name "Net-(JP16-Pad2)") (class "Default")
      (node (ref "JP16") (pin "2") (pinfunction "2_2") (pintype "passive"))
      (node (ref "JP17") (pin "3") (pinfunction "3_3") (pintype "passive"))
    )
    (net (code "34") (name "Net-(LED1-PadA)") (class "Default")
      (node (ref "LED1") (pin "A") (pinfunction "A_A") (pintype "passive"))
      (node (ref "R27") (pin "1") (pinfunction "1_1") (pintype "passive"))
    )
    (net (code "35") (name "Net-(LED2-PadA)") (class "Default")
      (node (ref "LED2") (pin "A") (pinfunction "A_A") (pintype "passive"))
      (node (ref "R25") (pin "1") (pinfunction "1_1") (pintype "passive"))
    )
    (net (code "36") (name "Net-(LED3-PadA)") (class "Default")
      (node (ref "LED3") (pin "A") (pinfunction "A_A") (pintype "passive"))
      (node (ref "R28") (pin "1") (pinfunction "1_1") (pintype "passive"))
    )
    (net (code "37") (name "Net-(LED4-PadA)") (class "Default")
      (node (ref "LED4") (pin "A") (pinfunction "A_A") (pintype "passive"))
      (node (ref "R26") (pin "2") (pinfunction "2_2") (pintype "passive"))
    )
    (net (code "38") (name "Net-(LED5-PadA)") (class "Default")
      (node (ref "LED5") (pin "A") (pinfunction "A_A") (pintype "passive"))
      (node (ref "R18") (pin "1") (pinfunction "1_1") (pintype "passive"))
    )
    (net (code "39") (name "Net-(LED6-PadA)") (class "Default")
      (node (ref "LED6") (pin "A") (pinfunction "A_A") (pintype "passive"))
      (node (ref "R17") (pin "1") (pinfunction "1_1") (pintype "passive"))
    )
    (net (code "40") (name "Net-(R6-Pad1)") (class "Default")
      (node (ref "R6") (pin "1") (pinfunction "1_1") (pintype "passive"))
      (node (ref "R9") (pin "2") (pinfunction "2_2") (pintype "passive"))
      (node (ref "U$1") (pin "DIN") (pinfunction "DIN_DIN") (pintype "input"))
    )
    (net (code "41") (name "Net-(R10-Pad2)") (class "Default")
      (node (ref "R10") (pin "2") (pinfunction "2_2") (pintype "passive"))
      (node (ref "U$2") (pin "SIM_RST") (pinfunction "SIM_RST_SIM_RST") (pintype "bidirectional"))
    )
    (net (code "42") (name "Net-(R11-Pad2)") (class "Default")
      (node (ref "R11") (pin "2") (pinfunction "2_2") (pintype "passive"))
      (node (ref "U$2") (pin "SIM_CLK") (pinfunction "SIM_CLK_SIM_CLK") (pintype "bidirectional"))
    )
    (net (code "43") (name "Net-(R23-Pad1)") (class "Default")
      (node (ref "R23") (pin "1") (pinfunction "1_1") (pintype "passive"))
      (node (ref "R8") (pin "1") (pinfunction "1_1") (pintype "passive"))
      (node (ref "U$1") (pin "CS") (pinfunction "CS_CS") (pintype "bidirectional"))
    )
    (net (code "44") (name "Net-(R24-Pad2)") (class "Default")
      (node (ref "R24") (pin "2") (pinfunction "2_2") (pintype "passive"))
      (node (ref "R7") (pin "1") (pinfunction "1_1") (pintype "passive"))
      (node (ref "U$1") (pin "SCK") (pinfunction "SCK_SCK") (pintype "bidirectional"))
    )
    (net (code "45") (name "Net-(R35-Pad2)") (class "Default")
      (node (ref "R35") (pin "2") (pinfunction "2_2") (pintype "passive"))
      (node (ref "U$1") (pin "DOUT") (pinfunction "DOUT_DOUT") (pintype "output"))
    )
    (net (code "46") (name "Net-(R47-Pad2)") (class "Default")
      (node (ref "R47") (pin "2") (pinfunction "2_2") (pintype "passive"))
      (node (ref "U$2") (pin "SIM_DATA") (pinfunction "SIM_DATA_SIM_DATA") (pintype "bidirectional"))
    )
    (net (code "47") (name "Net-(T3-B)") (class "Default")
      (node (ref "JP10") (pin "1") (pinfunction "1_1") (pintype "passive"))
      (node (ref "T3") (pin "1") (pinfunction "B_1") (pintype "passive"))
    )
    (net (code "48") (name "Net-(T3-E)") (class "Default")
      (node (ref "R42") (pin "1") (pinfunction "1_1") (pintype "passive"))
      (node (ref "T3") (pin "2") (pinfunction "E_2") (pintype "passive"))
    )
    (net (code "49") (name "Net-(T4-B)") (class "Default")
      (node (ref "R48") (pin "1") (pinfunction "1_1") (pintype "passive"))
      (node (ref "T4") (pin "1") (pinfunction "B_1") (pintype "passive"))
    )
    (net (code "50") (name "Net-(T4-C)") (class "Default")
      (node (ref "R44") (pin "1") (pinfunction "1_1") (pintype "passive"))
      (node (ref "T4") (pin "3") (pinfunction "C_3") (pintype "passive"))
    )
    (net (code "51") (name "Net-(U1-(A10)PC2)") (class "Default")
      (node (ref "R27") (pin "2") (pinfunction "2_2") (pintype "passive"))
      (node (ref "U1") (pin "55") (pinfunction "(A10)PC2_55") (pintype "bidirectional"))
    )
    (net (code "52") (name "Net-(U1-(AD3)PA3)") (class "Default")
      (node (ref "R22") (pin "2") (pinfunction "2_2") (pintype "passive"))
      (node (ref "R36") (pin "1") (pinfunction "1_1") (pintype "passive"))
      (node (ref "U1") (pin "75") (pinfunction "(AD3)PA3_75") (pintype "bidirectional"))
    )
    (net (code "53") (name "Net-(U1-(AD4)PA4)") (class "Default")
      (node (ref "R19") (pin "2") (pinfunction "2_2") (pintype "passive"))
      (node (ref "R34") (pin "1") (pinfunction "1_1") (pintype "passive"))
      (node (ref "U1") (pin "74") (pinfunction "(AD4)PA4_74") (pintype "bidirectional"))
    )
    (net (code "54") (name "Net-(U1-(ADC1)PF1)") (class "Default")
      (node (ref "R20") (pin "1") (pinfunction "1_1") (pintype "passive"))
      (node (ref "R31") (pin "2") (pinfunction "2_2") (pintype "passive"))
      (node (ref "U1") (pin "96") (pinfunction "(ADC1)PF1_96") (pintype "bidirectional"))
    )
    (net (code "55") (name "Net-(U1-(ADC3)PF3)") (class "Default")
      (node (ref "DC17") (pin "1") (pinfunction "1_1") (pintype "passive"))
      (node (ref "R21") (pin "2") (pinfunction "2_2") (pintype "passive"))
      (node (ref "U1") (pin "94") (pinfunction "(ADC3)PF3_94") (pintype "bidirectional"))
    )
    (net (code "56") (name "Net-(U1-(MISO{slash}PCINT3)PB3)") (class "Default")
      (node (ref "JP4") (pin "1") (pinfunction "1_1") (pintype "passive"))
      (node (ref "R35") (pin "1") (pinfunction "1_1") (pintype "passive"))
      (node (ref "U1") (pin "22") (pinfunction "(MISO/PCINT3)PB3_22") (pintype "bidirectional"))
    )
    (net (code "57") (name "Net-(U1-(MOSI{slash}PCINT2)PB2)") (class "Default")
      (node (ref "JP4") (pin "3") (pinfunction "3_3") (pintype "passive"))
      (node (ref "R6") (pin "2") (pinfunction "2_2") (pintype "passive"))
      (node (ref "U1") (pin "21") (pinfunction "(MOSI/PCINT2)PB2_21") (pintype "bidirectional"))
    )
    (net (code "58") (name "Net-(U1-(OC0B)PG5)") (class "Default")
      (node (ref "R39") (pin "1") (pinfunction "1_1") (pintype "passive"))
      (node (ref "R40") (pin "2") (pinfunction "2_2") (pintype "passive"))
      (node (ref "U1") (pin "1") (pinfunction "(OC0B)PG5_1") (pintype "bidirectional"))
    )
    (net (code "59") (name "Net-(U1-(OC1B{slash}PCINT6)PB6)") (class "Default")
      (node (ref "R25") (pin "2") (pinfunction "2_2") (pintype "passive"))
      (node (ref "U1") (pin "25") (pinfunction "(OC1B/PCINT6)PB6_25") (pintype "bidirectional"))
    )
    (net (code "60") (name "Net-(U1-(RXD0{slash}PCIN8)PE0)") (class "Default")
      (node (ref "JP5") (pin "4") (pinfunction "4_4") (pintype "passive"))
      (node (ref "U1") (pin "2") (pinfunction "(RXD0/PCIN8)PE0_2") (pintype "bidirectional"))
    )
    (net (code "61") (name "Net-(U1-(RXD1{slash}INT2)PD2)") (class "Default")
      (node (ref "R15") (pin "2") (pinfunction "2_2") (pintype "passive"))
      (node (ref "U1") (pin "45") (pinfunction "(RXD1/INT2)PD2_45") (pintype "bidirectional"))
    )
    (net (code "62") (name "Net-(U1-(SCK{slash}PCINT1)PB1)") (class "Default")
      (node (ref "JP4") (pin "5") (pinfunction "5_5") (pintype "passive"))
      (node (ref "R7") (pin "2") (pinfunction "2_2") (pintype "passive"))
      (node (ref "U1") (pin "20") (pinfunction "(SCK/PCINT1)PB1_20") (pintype "bidirectional"))
    )
    (net (code "63") (name "Net-(U1-(SCL{slash}INT0)PD0)") (class "Default")
      (node (ref "R30") (pin "1") (pinfunction "1_1") (pintype "passive"))
      (node (ref "U1") (pin "43") (pinfunction "(SCL/INT0)PD0_43") (pintype "bidirectional"))
    )
    (net (code "64") (name "Net-(U1-(SDA{slash}INT1)PD1)") (class "Default")
      (node (ref "R5") (pin "1") (pinfunction "1_1") (pintype "passive"))
      (node (ref "U1") (pin "44") (pinfunction "(SDA/INT1)PD1_44") (pintype "bidirectional"))
    )
    (net (code "65") (name "Net-(U1-(SS{slash}PCINT0)PB0)") (class "Default")
      (node (ref "R8") (pin "2") (pinfunction "2_2") (pintype "passive"))
      (node (ref "U1") (pin "19") (pinfunction "(SS/PCINT0)PB0_19") (pintype "bidirectional"))
    )
    (net (code "66") (name "Net-(U1-(TXD0)PE1)") (class "Default")
      (node (ref "JP5") (pin "3") (pinfunction "3_3") (pintype "passive"))
      (node (ref "U1") (pin "3") (pinfunction "(TXD0)PE1_3") (pintype "bidirectional"))
    )
    (net (code "67") (name "Net-(U1-(TXD1{slash}INT3)PD3)") (class "Default")
      (node (ref "R14") (pin "2") (pinfunction "2_2") (pintype "passive"))
      (node (ref "U1") (pin "46") (pinfunction "(TXD1/INT3)PD3_46") (pintype "bidirectional"))
    )
    (net (code "68") (name "Net-(U1-(WR)PG0)") (class "Default")
      (node (ref "R28") (pin "2") (pinfunction "2_2") (pintype "passive"))
      (node (ref "U1") (pin "51") (pinfunction "(WR)PG0_51") (pintype "bidirectional"))
    )
    (net (code "69") (name "Net-(U1-PH0(RXD2))") (class "Default")
      (node (ref "R13") (pin "1") (pinfunction "1_1") (pintype "passive"))
      (node (ref "U1") (pin "12") (pinfunction "PH0(RXD2)_12") (pintype "bidirectional"))
    )
    (net (code "70") (name "Net-(U1-PH1(TXD2))") (class "Default")
      (node (ref "R12") (pin "1") (pinfunction "1_1") (pintype "passive"))
      (node (ref "U1") (pin "13") (pinfunction "PH1(TXD2)_13") (pintype "bidirectional"))
    )
    (net (code "71") (name "Net-(U1-PJ0(RXD3{slash}PCINT9))") (class "Default")
      (node (ref "R32") (pin "1") (pinfunction "1_1") (pintype "passive"))
      (node (ref "U1") (pin "63") (pinfunction "PJ0(RXD3/PCINT9)_63") (pintype "bidirectional"))
    )
    (net (code "72") (name "Net-(U1-PJ1(TXD3{slash}PCINT10))") (class "Default")
      (node (ref "R33") (pin "1") (pinfunction "1_1") (pintype "passive"))
      (node (ref "U1") (pin "64") (pinfunction "PJ1(TXD3/PCINT10)_64") (pintype "bidirectional"))
    )
    (net (code "73") (name "Net-(U1-PK4(ADC12{slash}PCINT20))") (class "Default")
      (node (ref "DC14") (pin "2") (pinfunction "2_2") (pintype "passive"))
      (node (ref "R42") (pin "2") (pinfunction "2_2") (pintype "passive"))
      (node (ref "U1") (pin "85") (pinfunction "PK4(ADC12/PCINT20)_85") (pintype "bidirectional"))
    )
    (net (code "74") (name "Net-(U1-PK5(ADC13{slash}PCINT21))") (class "Default")
      (node (ref "R48") (pin "2") (pinfunction "2_2") (pintype "passive"))
      (node (ref "U1") (pin "84") (pinfunction "PK5(ADC13/PCINT21)_84") (pintype "bidirectional"))
    )
    (net (code "75") (name "Net-(U1-PK6(ADC14{slash}PCINT22))") (class "Default")
      (node (ref "R43") (pin "2") (pinfunction "2_2") (pintype "passive"))
      (node (ref "R44") (pin "2") (pinfunction "2_2") (pintype "passive"))
      (node (ref "U1") (pin "83") (pinfunction "PK6(ADC14/PCINT22)_83") (pintype "bidirectional"))
    )
    (net (code "76") (name "Net-(U1-PK7(ADC15{slash}PCINT23))") (class "Default")
      (node (ref "DC21") (pin "1") (pinfunction "1_1") (pintype "passive"))
      (node (ref "R1") (pin "1") (pinfunction "1_1") (pintype "passive"))
      (node (ref "U1") (pin "82") (pinfunction "PK7(ADC15/PCINT23)_82") (pintype "bidirectional"))
    )
    (net (code "77") (name "Net-(U1-RESET)") (class "Default")
      (node (ref "DC11") (pin "1") (pinfunction "1_1") (pintype "passive"))
      (node (ref "JP4") (pin "2") (pinfunction "2_2") (pintype "passive"))
      (node (ref "JP5") (pin "2") (pinfunction "2_2") (pintype "passive"))
      (node (ref "R16") (pin "2") (pinfunction "2_2") (pintype "passive"))
      (node (ref "U1") (pin "30") (pinfunction "RESET_30") (pintype "input"))
    )
    (net (code "78") (name "Net-(U1-XTAL1)") (class "Default")
      (node (ref "C8") (pin "2") (pinfunction "2_2") (pintype "passive"))
      (node (ref "O1") (pin "1") (pinfunction "1_1") (pintype "passive"))
      (node (ref "U1") (pin "34") (pinfunction "XTAL1_34") (pintype "input"))
    )
    (net (code "79") (name "Net-(U1-XTAL2)") (class "Default")
      (node (ref "C7") (pin "2") (pinfunction "2_2") (pintype "passive"))
      (node (ref "O1") (pin "2") (pinfunction "2_2") (pintype "passive"))
      (node (ref "U1") (pin "33") (pinfunction "XTAL2_33") (pintype "output"))
    )
    (net (code "80") (name "Net-(U2-NETLIGHT)") (class "Default")
      (node (ref "R17") (pin "2") (pinfunction "2_2") (pintype "passive"))
      (node (ref "U2") (pin "13") (pinfunction "NETLIGHT_13") (pintype "output"))
    )
    (net (code "81") (name "Net-(U2-RF_ANT)") (class "Default")
      (node (ref "U2") (pin "39") (pinfunction "RF_ANT_39") (pintype "bidirectional"))
      (node (ref "X1") (pin "1") (pinfunction "1_1") (pintype "passive"))
    )
    (net (code "82") (name "Net-(U2-RXD)") (class "Default")
      (node (ref "R14") (pin "1") (pinfunction "1_1") (pintype "passive"))
      (node (ref "R29") (pin "2") (pinfunction "2_2") (pintype "passive"))
      (node (ref "U2") (pin "21") (pinfunction "RXD_21") (pintype "input"))
    )
    (net (code "83") (name "Net-(U2-SIM_CLK)") (class "Default")
      (node (ref "R11") (pin "1") (pinfunction "1_1") (pintype "passive"))
      (node (ref "U2") (pin "30") (pinfunction "SIM_CLK_30") (pintype "output"))
    )
    (net (code "84") (name "Net-(U2-SIM_DATA)") (class "Default")
      (node (ref "R47") (pin "1") (pinfunction "1_1") (pintype "passive"))
      (node (ref "U2") (pin "29") (pinfunction "SIM_DATA_29") (pintype "bidirectional"))
    )
    (net (code "85") (name "Net-(U2-SIM_GND)") (class "Default")
      (node (ref "DC15") (pin "1") (pinfunction "1_1") (pintype "passive"))
      (node (ref "U$2") (pin "SIM_GND") (pinfunction "SIM_GND_SIM_GND") (pintype "bidirectional"))
      (node (ref "U2") (pin "31") (pinfunction "SIM_GND_31") (pintype "power_in"))
    )
    (net (code "86") (name "Net-(U2-SIM_RST)") (class "Default")
      (node (ref "R10") (pin "1") (pinfunction "1_1") (pintype "passive"))
      (node (ref "U2") (pin "28") (pinfunction "SIM_RST_28") (pintype "output"))
    )
    (net (code "87") (name "Net-(U2-SIM_VDD)") (class "Default")
      (node (ref "DC15") (pin "2") (pinfunction "2_2") (pintype "passive"))
      (node (ref "U$2") (pin "SIM_VDD") (pinfunction "SIM_VDD_SIM_VDD") (pintype "bidirectional"))
      (node (ref "U2") (pin "27") (pinfunction "SIM_VDD_27") (pintype "power_in"))
    )
    (net (code "88") (name "Net-(U2-TXD)") (class "Default")
      (node (ref "R15") (pin "1") (pinfunction "1_1") (pintype "passive"))
      (node (ref "U2") (pin "22") (pinfunction "TXD_22") (pintype "output"))
    )
    (net (code "89") (name "Net-(U3-RX)") (class "Default")
      (node (ref "R12") (pin "2") (pinfunction "2_2") (pintype "passive"))
      (node (ref "R4") (pin "2") (pinfunction "2_2") (pintype "passive"))
      (node (ref "U3") (pin "1") (pinfunction "RX_1") (pintype "input"))
    )
    (net (code "90") (name "Net-(U3-TX)") (class "Default")
      (node (ref "R13") (pin "2") (pinfunction "2_2") (pintype "passive"))
      (node (ref "U3") (pin "2") (pinfunction "TX_2") (pintype "output"))
    )
    (net (code "91") (name "Net-(U4-ADJ)") (class "Default")
      (node (ref "R49") (pin "1") (pinfunction "1_1") (pintype "passive"))
      (node (ref "R50") (pin "2") (pinfunction "2_2") (pintype "passive"))
      (node (ref "U4") (pin "1") (pinfunction "ADJ_1") (pintype "input"))
    )
    (net (code "92") (name "VDD") (class "Default")
      (node (ref "DC1") (pin "1") (pinfunction "1_1") (pintype "passive"))
      (node (ref "DC18") (pin "2") (pinfunction "2_2") (pintype "passive"))
      (node (ref "DC2") (pin "1") (pinfunction "1_1") (pintype "passive"))
      (node (ref "DC3") (pin "1") (pinfunction "1_1") (pintype "passive"))
      (node (ref "DC4") (pin "1") (pinfunction "1_1") (pintype "passive"))
      (node (ref "DC5") (pin "1") (pinfunction "1_1") (pintype "passive"))
      (node (ref "L1") (pin "2") (pinfunction "2_2") (pintype "passive"))
      (node (ref "R20") (pin "2") (pinfunction "2_2") (pintype "passive"))
      (node (ref "R40") (pin "1") (pinfunction "1_1") (pintype "passive"))
      (node (ref "U1") (pin "10") (pinfunction "VCC_10") (pintype "power_in"))
      (node (ref "U1") (pin "100") (pinfunction "AVCC_100") (pintype "power_in"))
      (node (ref "U1") (pin "31") (pinfunction "VCC1_31") (pintype "power_in"))
      (node (ref "U1") (pin "61") (pinfunction "VCC2_61") (pintype "power_in"))
      (node (ref "U1") (pin "80") (pinfunction "VCC3_80") (pintype "power_in"))
    )
    (net (code "93") (name "unconnected-(IC3-I+_1-Pad2)") (class "Default")
      (node (ref "IC3") (pin "2") (pinfunction "I+_1_2") (pintype "bidirectional"))
    )
    (net (code "94") (name "unconnected-(IC3-I-_0-Pad3)") (class "Default")
      (node (ref "IC3") (pin "3") (pinfunction "I-_0_3") (pintype "bidirectional"))
    )
    (net (code "95") (name "unconnected-(JP12-Pad2)") (class "Default")
      (node (ref "JP12") (pin "2") (pinfunction "2_2") (pintype "passive"))
    )
    (net (code "96") (name "unconnected-(JP15-Pad2)") (class "Default")
      (node (ref "JP15") (pin "2") (pinfunction "2_2") (pintype "passive"))
    )
    (net (code "97") (name "unconnected-(U$1-PadCD)") (class "Default")
      (node (ref "U$1") (pin "CD") (pinfunction "CD_CD") (pintype "output"))
    )
    (net (code "98") (name "unconnected-(U1-(A8)PC0-Pad53)") (class "Default")
      (node (ref "U1") (pin "53") (pinfunction "(A8)PC0_53") (pintype "bidirectional"))
    )
    (net (code "99") (name "unconnected-(U1-(A9)PC1-Pad54)") (class "Default")
      (node (ref "U1") (pin "54") (pinfunction "(A9)PC1_54") (pintype "bidirectional"))
    )
    (net (code "100") (name "unconnected-(U1-(A11)PC3-Pad56)") (class "Default")
      (node (ref "U1") (pin "56") (pinfunction "(A11)PC3_56") (pintype "bidirectional"))
    )
    (net (code "101") (name "unconnected-(U1-(A12)PC4-Pad57)") (class "Default")
      (node (ref "U1") (pin "57") (pinfunction "(A12)PC4_57") (pintype "bidirectional"))
    )
    (net (code "102") (name "unconnected-(U1-(A13)PC5-Pad58)") (class "Default")
      (node (ref "U1") (pin "58") (pinfunction "(A13)PC5_58") (pintype "bidirectional"))
    )
    (net (code "103") (name "unconnected-(U1-(A14)PC6-Pad59)") (class "Default")
      (node (ref "U1") (pin "59") (pinfunction "(A14)PC6_59") (pintype "bidirectional"))
    )
    (net (code "104") (name "unconnected-(U1-(A15)PC7-Pad60)") (class "Default")
      (node (ref "U1") (pin "60") (pinfunction "(A15)PC7_60") (pintype "bidirectional"))
    )
    (net (code "105") (name "unconnected-(U1-(AD0)PA0-Pad78)") (class "Default")
      (node (ref "U1") (pin "78") (pinfunction "(AD0)PA0_78") (pintype "bidirectional"))
    )
    (net (code "106") (name "unconnected-(U1-(AD1)PA1-Pad77)") (class "Default")
      (node (ref "U1") (pin "77") (pinfunction "(AD1)PA1_77") (pintype "bidirectional"))
    )
    (net (code "107") (name "unconnected-(U1-(AD2)PA2-Pad76)") (class "Default")
      (node (ref "U1") (pin "76") (pinfunction "(AD2)PA2_76") (pintype "bidirectional"))
    )
    (net (code "108") (name "unconnected-(U1-(AD5)PA5-Pad73)") (class "Default")
      (node (ref "U1") (pin "73") (pinfunction "(AD5)PA5_73") (pintype "bidirectional"))
    )
    (net (code "109") (name "unconnected-(U1-(AD6)PA6-Pad72)") (class "Default")
      (node (ref "U1") (pin "72") (pinfunction "(AD6)PA6_72") (pintype "bidirectional"))
    )
    (net (code "110") (name "unconnected-(U1-(AD7)PA7-Pad71)") (class "Default")
      (node (ref "U1") (pin "71") (pinfunction "(AD7)PA7_71") (pintype "bidirectional"))
    )
    (net (code "111") (name "unconnected-(U1-(ADC0)PF0-Pad97)") (class "Default")
      (node (ref "U1") (pin "97") (pinfunction "(ADC0)PF0_97") (pintype "bidirectional"))
    )
    (net (code "112") (name "unconnected-(U1-(ADC2)PF2-Pad95)") (class "Default")
      (node (ref "U1") (pin "95") (pinfunction "(ADC2)PF2_95") (pintype "bidirectional"))
    )
    (net (code "113") (name "unconnected-(U1-(ADC4{slash}TCK)PF4-Pad93)") (class "Default")
      (node (ref "U1") (pin "93") (pinfunction "(ADC4/TCK)PF4_93") (pintype "bidirectional"))
    )
    (net (code "114") (name "unconnected-(U1-(ADC5{slash}TMS)PF5-Pad92)") (class "Default")
      (node (ref "U1") (pin "92") (pinfunction "(ADC5/TMS)PF5_92") (pintype "bidirectional"))
    )
    (net (code "115") (name "unconnected-(U1-(ADC6{slash}TDO)PF6-Pad91)") (class "Default")
      (node (ref "U1") (pin "91") (pinfunction "(ADC6/TDO)PF6_91") (pintype "bidirectional"))
    )
    (net (code "116") (name "unconnected-(U1-(ADC7{slash}TDI)PF7-Pad90)") (class "Default")
      (node (ref "U1") (pin "90") (pinfunction "(ADC7/TDI)PF7_90") (pintype "bidirectional"))
    )
    (net (code "117") (name "unconnected-(U1-(ALE)PG2-Pad70)") (class "Default")
      (node (ref "U1") (pin "70") (pinfunction "(ALE)PG2_70") (pintype "bidirectional"))
    )
    (net (code "118") (name "unconnected-(U1-(CLKO{slash}ICP3{slash}INT7)PE7-Pad9)") (class "Default")
      (node (ref "U1") (pin "9") (pinfunction "(CLKO/ICP3/INT7)PE7_9") (pintype "bidirectional"))
    )
    (net (code "119") (name "unconnected-(U1-(ICP1)PD4-Pad47)") (class "Default")
      (node (ref "U1") (pin "47") (pinfunction "(ICP1)PD4_47") (pintype "bidirectional"))
    )
    (net (code "120") (name "unconnected-(U1-(OC0A{slash}OC1C{slash}PCINT7)PB7-Pad26)") (class "Default")
      (node (ref "U1") (pin "26") (pinfunction "(OC0A/OC1C/PCINT7)PB7_26") (pintype "bidirectional"))
    )
    (net (code "121") (name "unconnected-(U1-(OC1A{slash}PCINT5)PB5-Pad24)") (class "Default")
      (node (ref "U1") (pin "24") (pinfunction "(OC1A/PCINT5)PB5_24") (pintype "bidirectional"))
    )
    (net (code "122") (name "unconnected-(U1-(OC2A{slash}PCINT4)PB4-Pad23)") (class "Default")
      (node (ref "U1") (pin "23") (pinfunction "(OC2A/PCINT4)PB4_23") (pintype "bidirectional"))
    )
    (net (code "123") (name "unconnected-(U1-(OC3A{slash}AIN1)PE3-Pad5)") (class "Default")
      (node (ref "U1") (pin "5") (pinfunction "(OC3A/AIN1)PE3_5") (pintype "bidirectional"))
    )
    (net (code "124") (name "unconnected-(U1-(OC3B{slash}INT4)PE4-Pad6)") (class "Default")
      (node (ref "U1") (pin "6") (pinfunction "(OC3B/INT4)PE4_6") (pintype "bidirectional"))
    )
    (net (code "125") (name "unconnected-(U1-(OC3C{slash}INT5)PE5-Pad7)") (class "Default")
      (node (ref "U1") (pin "7") (pinfunction "(OC3C/INT5)PE5_7") (pintype "bidirectional"))
    )
    (net (code "126") (name "unconnected-(U1-(RD)PG1-Pad52)") (class "Default")
      (node (ref "U1") (pin "52") (pinfunction "(RD)PG1_52") (pintype "bidirectional"))
    )
    (net (code "127") (name "unconnected-(U1-(T0)PD7-Pad50)") (class "Default")
      (node (ref "U1") (pin "50") (pinfunction "(T0)PD7_50") (pintype "bidirectional"))
    )
    (net (code "128") (name "unconnected-(U1-(T1)PD6-Pad49)") (class "Default")
      (node (ref "U1") (pin "49") (pinfunction "(T1)PD6_49") (pintype "bidirectional"))
    )
    (net (code "129") (name "unconnected-(U1-(T3{slash}INT6)PE6-Pad8)") (class "Default")
      (node (ref "U1") (pin "8") (pinfunction "(T3/INT6)PE6_8") (pintype "bidirectional"))
    )
    (net (code "130") (name "unconnected-(U1-(TOSC1)PG4-Pad29)") (class "Default")
      (node (ref "U1") (pin "29") (pinfunction "(TOSC1)PG4_29") (pintype "bidirectional"))
    )
    (net (code "131") (name "unconnected-(U1-(TOSC2)PG3-Pad28)") (class "Default")
      (node (ref "U1") (pin "28") (pinfunction "(TOSC2)PG3_28") (pintype "bidirectional"))
    )
    (net (code "132") (name "unconnected-(U1-(XCK0{slash}AIN0)PE2-Pad4)") (class "Default")
      (node (ref "U1") (pin "4") (pinfunction "(XCK0/AIN0)PE2_4") (pintype "bidirectional"))
    )
    (net (code "133") (name "unconnected-(U1-(XCK1)PD5-Pad48)") (class "Default")
      (node (ref "U1") (pin "48") (pinfunction "(XCK1)PD5_48") (pintype "bidirectional"))
    )
    (net (code "134") (name "unconnected-(U1-AREF-Pad98)") (class "Default")
      (node (ref "U1") (pin "98") (pinfunction "AREF_98") (pintype "bidirectional"))
    )
    (net (code "135") (name "unconnected-(U1-PH2(XCK2)-Pad14)") (class "Default")
      (node (ref "U1") (pin "14") (pinfunction "PH2(XCK2)_14") (pintype "bidirectional"))
    )
    (net (code "136") (name "unconnected-(U1-PH3(OC4A)-Pad15)") (class "Default")
      (node (ref "U1") (pin "15") (pinfunction "PH3(OC4A)_15") (pintype "bidirectional"))
    )
    (net (code "137") (name "unconnected-(U1-PH4(OC4B)-Pad16)") (class "Default")
      (node (ref "U1") (pin "16") (pinfunction "PH4(OC4B)_16") (pintype "bidirectional"))
    )
    (net (code "138") (name "unconnected-(U1-PH5(OC4C)-Pad17)") (class "Default")
      (node (ref "U1") (pin "17") (pinfunction "PH5(OC4C)_17") (pintype "bidirectional"))
    )
    (net (code "139") (name "unconnected-(U1-PH6(OC2B)-Pad18)") (class "Default")
      (node (ref "U1") (pin "18") (pinfunction "PH6(OC2B)_18") (pintype "bidirectional"))
    )
    (net (code "140") (name "unconnected-(U1-PH7(T4)-Pad27)") (class "Default")
      (node (ref "U1") (pin "27") (pinfunction "PH7(T4)_27") (pintype "bidirectional"))
    )
    (net (code "141") (name "unconnected-(U1-PJ2(XCK3{slash}PCINT11)-Pad65)") (class "Default")
      (node (ref "U1") (pin "65") (pinfunction "PJ2(XCK3/PCINT11)_65") (pintype "bidirectional"))
    )
    (net (code "142") (name "unconnected-(U1-PJ3(PCINT12)-Pad66)") (class "Default")
      (node (ref "U1") (pin "66") (pinfunction "PJ3(PCINT12)_66") (pintype "bidirectional"))
    )
    (net (code "143") (name "unconnected-(U1-PJ4(PCINT13)-Pad67)") (class "Default")
      (node (ref "U1") (pin "67") (pinfunction "PJ4(PCINT13)_67") (pintype "bidirectional"))
    )
    (net (code "144") (name "unconnected-(U1-PJ5(PCINT14)-Pad68)") (class "Default")
      (node (ref "U1") (pin "68") (pinfunction "PJ5(PCINT14)_68") (pintype "bidirectional"))
    )
    (net (code "145") (name "unconnected-(U1-PJ6(PCINT15)-Pad69)") (class "Default")
      (node (ref "U1") (pin "69") (pinfunction "PJ6(PCINT15)_69") (pintype "bidirectional"))
    )
    (net (code "146") (name "unconnected-(U1-PJ7-Pad79)") (class "Default")
      (node (ref "U1") (pin "79") (pinfunction "PJ7_79") (pintype "bidirectional"))
    )
    (net (code "147") (name "unconnected-(U1-PK0(ADC8{slash}PCINT16)-Pad89)") (class "Default")
      (node (ref "U1") (pin "89") (pinfunction "PK0(ADC8/PCINT16)_89") (pintype "bidirectional"))
    )
    (net (code "148") (name "unconnected-(U1-PK1(ADC9{slash}PCINT17)-Pad88)") (class "Default")
      (node (ref "U1") (pin "88") (pinfunction "PK1(ADC9/PCINT17)_88") (pintype "bidirectional"))
    )
    (net (code "149") (name "unconnected-(U1-PK2(ADC10{slash}PCINT18)-Pad87)") (class "Default")
      (node (ref "U1") (pin "87") (pinfunction "PK2(ADC10/PCINT18)_87") (pintype "bidirectional"))
    )
    (net (code "150") (name "unconnected-(U1-PK3(ADC11{slash}PCINT19)-Pad86)") (class "Default")
      (node (ref "U1") (pin "86") (pinfunction "PK3(ADC11/PCINT19)_86") (pintype "bidirectional"))
    )
    (net (code "151") (name "unconnected-(U1-PL0(ICP4)-Pad35)") (class "Default")
      (node (ref "U1") (pin "35") (pinfunction "PL0(ICP4)_35") (pintype "bidirectional"))
    )
    (net (code "152") (name "unconnected-(U1-PL1(ICP5)-Pad36)") (class "Default")
      (node (ref "U1") (pin "36") (pinfunction "PL1(ICP5)_36") (pintype "bidirectional"))
    )
    (net (code "153") (name "unconnected-(U1-PL2(T5)-Pad37)") (class "Default")
      (node (ref "U1") (pin "37") (pinfunction "PL2(T5)_37") (pintype "bidirectional"))
    )
    (net (code "154") (name "unconnected-(U1-PL3(OC5A)-Pad38)") (class "Default")
      (node (ref "U1") (pin "38") (pinfunction "PL3(OC5A)_38") (pintype "bidirectional"))
    )
    (net (code "155") (name "unconnected-(U1-PL4(OC5B)-Pad39)") (class "Default")
      (node (ref "U1") (pin "39") (pinfunction "PL4(OC5B)_39") (pintype "bidirectional"))
    )
    (net (code "156") (name "unconnected-(U1-PL5(OC5C)-Pad40)") (class "Default")
      (node (ref "U1") (pin "40") (pinfunction "PL5(OC5C)_40") (pintype "bidirectional"))
    )
    (net (code "157") (name "unconnected-(U1-PL6-Pad41)") (class "Default")
      (node (ref "U1") (pin "41") (pinfunction "PL6_41") (pintype "bidirectional"))
    )
    (net (code "158") (name "unconnected-(U1-PL7-Pad42)") (class "Default")
      (node (ref "U1") (pin "42") (pinfunction "PL7_42") (pintype "bidirectional"))
    )
    (net (code "159") (name "unconnected-(U2-CTS-Pad23)") (class "Default")
      (node (ref "U2") (pin "23") (pinfunction "CTS_23") (pintype "output"))
    )
    (net (code "160") (name "unconnected-(U2-DBG_RXD-Pad14)") (class "Default")
      (node (ref "U2") (pin "14") (pinfunction "DBG_RXD_14") (pintype "input"))
    )
    (net (code "161") (name "unconnected-(U2-DBG_TXD-Pad15)") (class "Default")
      (node (ref "U2") (pin "15") (pinfunction "DBG_TXD_15") (pintype "output"))
    )
    (net (code "162") (name "unconnected-(U2-DCD-Pad25)") (class "Default")
      (node (ref "U2") (pin "25") (pinfunction "DCD_25") (pintype "output"))
    )
    (net (code "163") (name "unconnected-(U2-DTR-Pad20)") (class "Default")
      (node (ref "U2") (pin "20") (pinfunction "DTR_20") (pintype "input"))
    )
    (net (code "164") (name "unconnected-(U2-EMERG_OFF-Pad11)") (class "Default")
      (node (ref "U2") (pin "11") (pinfunction "EMERG_OFF_11") (pintype "input"))
    )
    (net (code "165") (name "unconnected-(U2-LOUDSPKN-Pad8)") (class "Default")
      (node (ref "U2") (pin "8") (pinfunction "LOUDSPKN_8") (pintype "output"))
    )
    (net (code "166") (name "unconnected-(U2-LOUDSPKP-Pad9)") (class "Default")
      (node (ref "U2") (pin "9") (pinfunction "LOUDSPKP_9") (pintype "output"))
    )
    (net (code "167") (name "unconnected-(U2-MIC1N-Pad5)") (class "Default")
      (node (ref "U2") (pin "5") (pinfunction "MIC1N_5") (pintype "input"))
    )
    (net (code "168") (name "unconnected-(U2-MIC1P-Pad4)") (class "Default")
      (node (ref "U2") (pin "4") (pinfunction "MIC1P_4") (pintype "input"))
    )
    (net (code "169") (name "unconnected-(U2-MIC2N-Pad3)") (class "Default")
      (node (ref "U2") (pin "3") (pinfunction "MIC2N_3") (pintype "input"))
    )
    (net (code "170") (name "unconnected-(U2-MIC2P-Pad2)") (class "Default")
      (node (ref "U2") (pin "2") (pinfunction "MIC2P_2") (pintype "input"))
    )
    (net (code "171") (name "unconnected-(U2-RI-Pad26)") (class "Default")
      (node (ref "U2") (pin "26") (pinfunction "RI_26") (pintype "output"))
    )
    (net (code "172") (name "unconnected-(U2-RTS-Pad24)") (class "Default")
      (node (ref "U2") (pin "24") (pinfunction "RTS_24") (pintype "input"))
    )
    (net (code "173") (name "unconnected-(U2-SPK1N-Pad6)") (class "Default")
      (node (ref "U2") (pin "6") (pinfunction "SPK1N_6") (pintype "output"))
    )
    (net (code "174") (name "unconnected-(U2-SPK1P-Pad7)") (class "Default")
      (node (ref "U2") (pin "7") (pinfunction "SPK1P_7") (pintype "output"))
    )
    (net (code "175") (name "unconnected-(U2-STATUS-Pad12)") (class "Default")
      (node (ref "U2") (pin "12") (pinfunction "STATUS_12") (pintype "output"))
    )
    (net (code "176") (name "unconnected-(U3-1PPS-Pad6)") (class "Default")
      (node (ref "U3") (pin "6") (pinfunction "1PPS_6") (pintype "bidirectional"))
    )
    (net (code "177") (name "unconnected-(U3-EXT_ANT-Pad11)") (class "Default")
      (node (ref "U3") (pin "11") (pinfunction "EXT_ANT_11") (pintype "bidirectional"))
    )
    (net (code "178") (name "unconnected-(U3-NC-Pad8)") (class "Default")
      (node (ref "U3") (pin "8") (pinfunction "NC_8") (pintype "no_connect"))
    )
    (net (code "179") (name "unconnected-(U3-NC-Pad9)") (class "Default")
      (node (ref "U3") (pin "9") (pinfunction "NC_9") (pintype "no_connect"))
    )
    (net (code "180") (name "unconnected-(U3-TIMER-Pad7)") (class "Default")
      (node (ref "U3") (pin "7") (pinfunction "TIMER_7") (pintype "bidirectional"))
    )
    (net (code "181") (name "unconnected-(U3-~{RESET}-Pad10)") (class "Default")
      (node (ref "U3") (pin "10") (pinfunction "~{RESET}_10") (pintype "input"))
    )
  )
)
